# Grownetics_12_Channel_CT_Shield.net
KiCad netlist of a schematic drawn in EAGLE
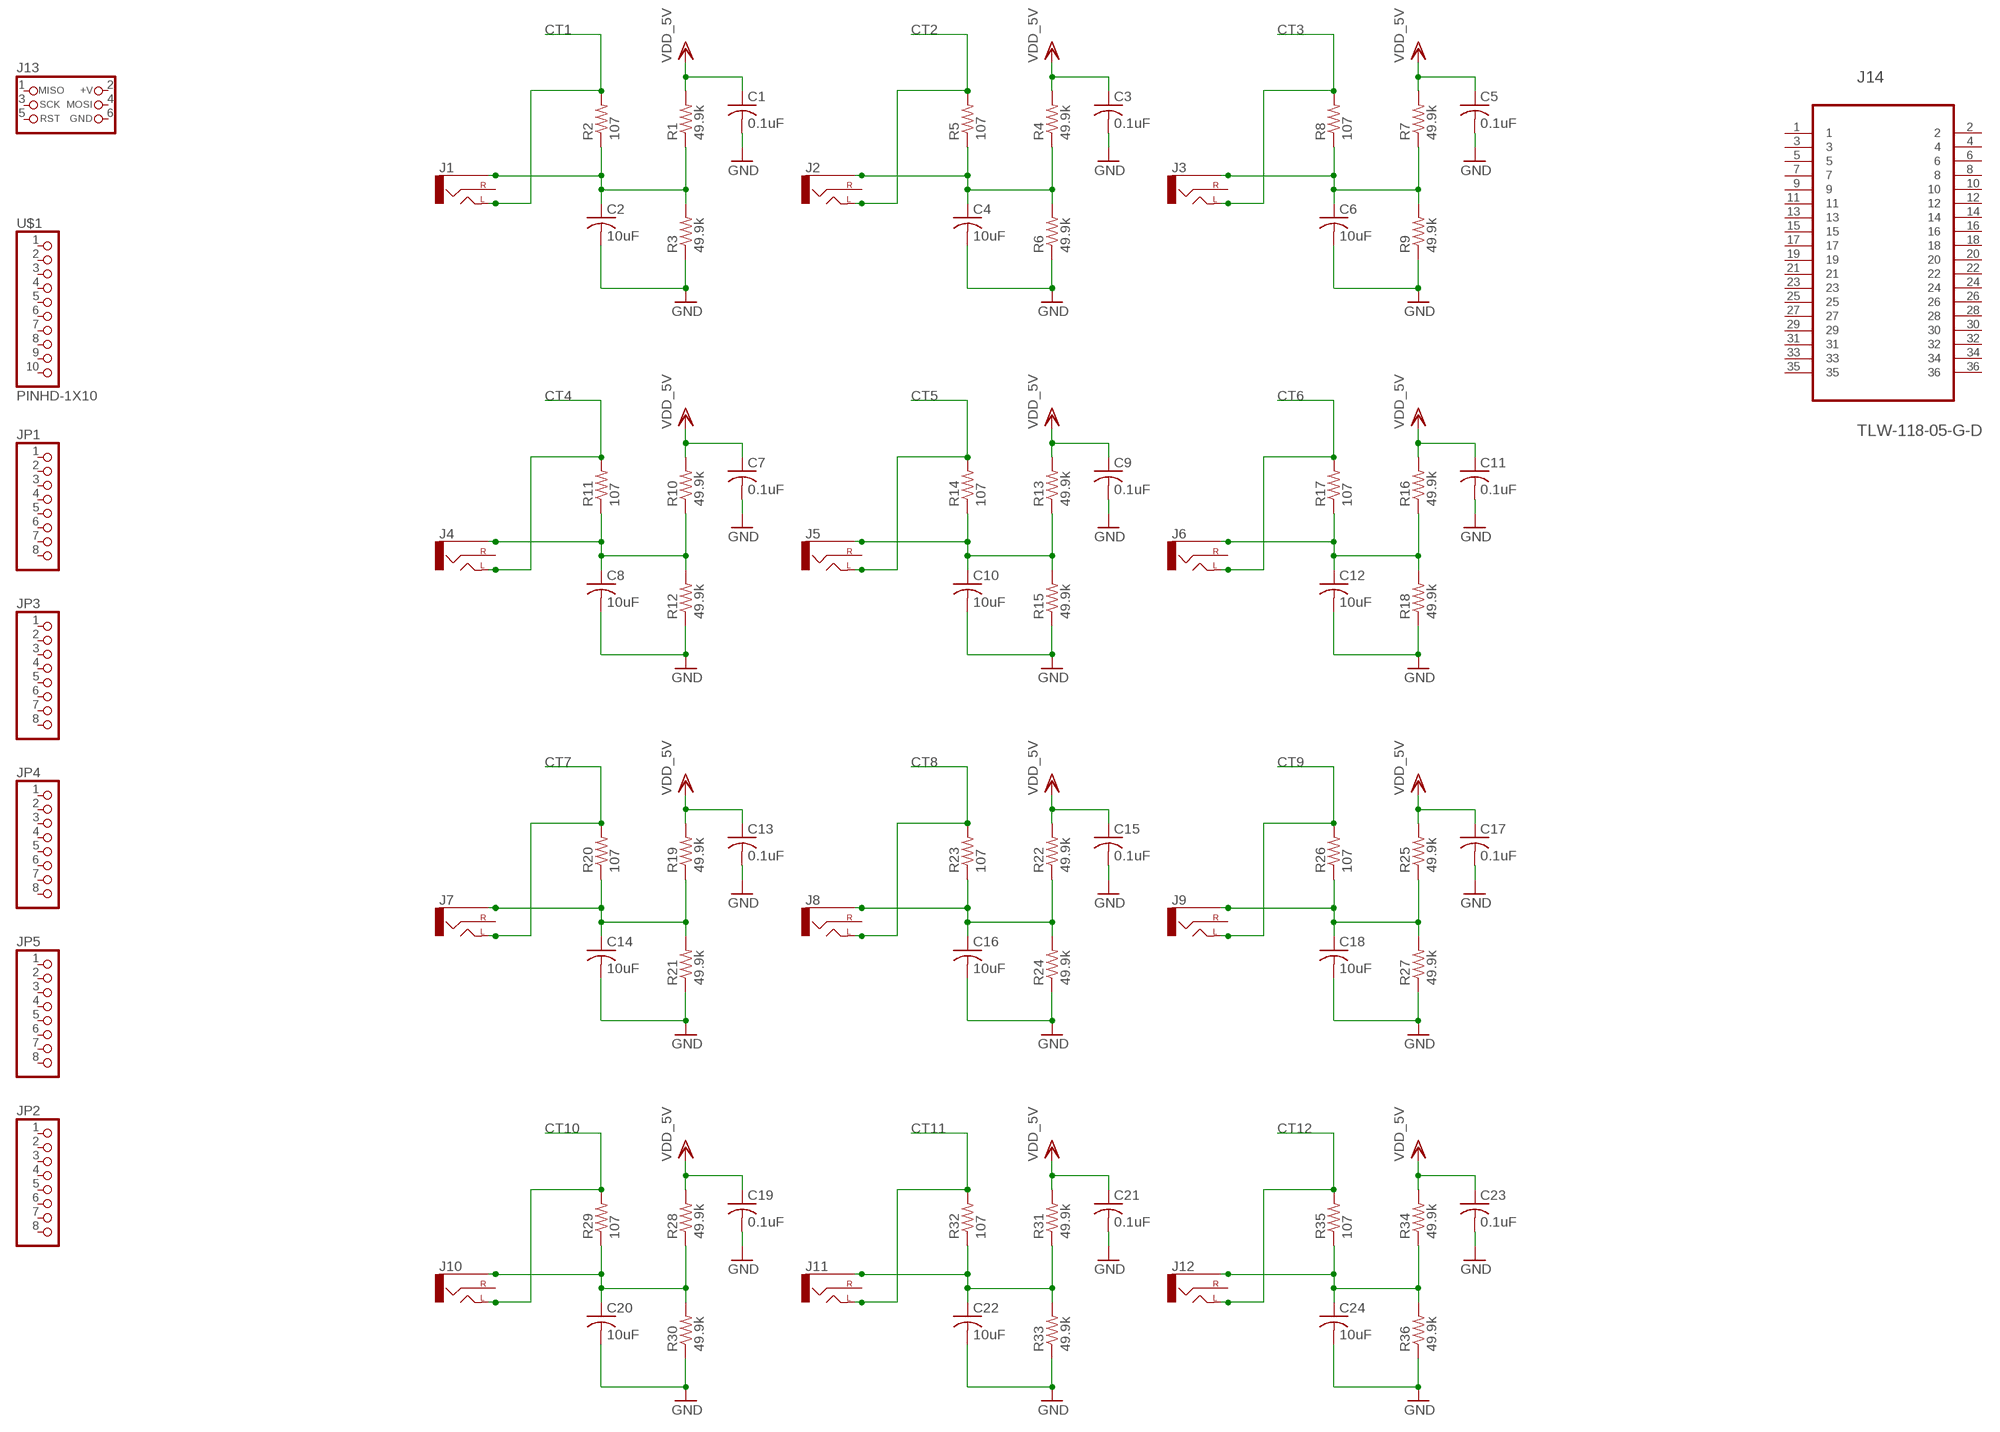
[diagram p0: schematic, sheet 1]

(export (version "E")
  (design (tool "Eeschema 10.0.6"))
  (components
    (comp (ref "C1")
      (value "0.1uF")
      (footprint "eagle-import:C0805")
      (libsource (lib "eagle-import") (part "C-USC0805"))
    )
    (comp (ref "C2")
      (value "10uF")
      (footprint "eagle-import:C0805")
      (libsource (lib "eagle-import") (part "C-USC0805"))
    )
    (comp (ref "C3")
      (value "0.1uF")
      (footprint "eagle-import:C0805")
      (libsource (lib "eagle-import") (part "C-USC0805"))
    )
    (comp (ref "C4")
      (value "10uF")
      (footprint "eagle-import:C0805")
      (libsource (lib "eagle-import") (part "C-USC0805"))
    )
    (comp (ref "C5")
      (value "0.1uF")
      (footprint "eagle-import:C0805")
      (libsource (lib "eagle-import") (part "C-USC0805"))
    )
    (comp (ref "C6")
      (value "10uF")
      (footprint "eagle-import:C0805")
      (libsource (lib "eagle-import") (part "C-USC0805"))
    )
    (comp (ref "C7")
      (value "0.1uF")
      (footprint "eagle-import:C0805")
      (libsource (lib "eagle-import") (part "C-USC0805"))
    )
    (comp (ref "C8")
      (value "10uF")
      (footprint "eagle-import:C0805")
      (libsource (lib "eagle-import") (part "C-USC0805"))
    )
    (comp (ref "C9")
      (value "0.1uF")
      (footprint "eagle-import:C0805")
      (libsource (lib "eagle-import") (part "C-USC0805"))
    )
    (comp (ref "C10")
      (value "10uF")
      (footprint "eagle-import:C0805")
      (libsource (lib "eagle-import") (part "C-USC0805"))
    )
    (comp (ref "C11")
      (value "0.1uF")
      (footprint "eagle-import:C0805")
      (libsource (lib "eagle-import") (part "C-USC0805"))
    )
    (comp (ref "C12")
      (value "10uF")
      (footprint "eagle-import:C0805")
      (libsource (lib "eagle-import") (part "C-USC0805"))
    )
    (comp (ref "C13")
      (value "0.1uF")
      (footprint "eagle-import:C0805")
      (libsource (lib "eagle-import") (part "C-USC0805"))
    )
    (comp (ref "C14")
      (value "10uF")
      (footprint "eagle-import:C0805")
      (libsource (lib "eagle-import") (part "C-USC0805"))
    )
    (comp (ref "C15")
      (value "0.1uF")
      (footprint "eagle-import:C0805")
      (libsource (lib "eagle-import") (part "C-USC0805"))
    )
    (comp (ref "C16")
      (value "10uF")
      (footprint "eagle-import:C0805")
      (libsource (lib "eagle-import") (part "C-USC0805"))
    )
    (comp (ref "C17")
      (value "0.1uF")
      (footprint "eagle-import:C0805")
      (libsource (lib "eagle-import") (part "C-USC0805"))
    )
    (comp (ref "C18")
      (value "10uF")
      (footprint "eagle-import:C0805")
      (libsource (lib "eagle-import") (part "C-USC0805"))
    )
    (comp (ref "C19")
      (value "0.1uF")
      (footprint "eagle-import:C0805")
      (libsource (lib "eagle-import") (part "C-USC0805"))
    )
    (comp (ref "C20")
      (value "10uF")
      (footprint "eagle-import:C0805")
      (libsource (lib "eagle-import") (part "C-USC0805"))
    )
    (comp (ref "C21")
      (value "0.1uF")
      (footprint "eagle-import:C0805")
      (libsource (lib "eagle-import") (part "C-USC0805"))
    )
    (comp (ref "C22")
      (value "10uF")
      (footprint "eagle-import:C0805")
      (libsource (lib "eagle-import") (part "C-USC0805"))
    )
    (comp (ref "C23")
      (value "0.1uF")
      (footprint "eagle-import:C0805")
      (libsource (lib "eagle-import") (part "C-USC0805"))
    )
    (comp (ref "C24")
      (value "10uF")
      (footprint "eagle-import:C0805")
      (libsource (lib "eagle-import") (part "C-USC0805"))
    )
    (comp (ref "J1")
      (value "AUDIO-JACKSMD2")
      (footprint "eagle-import:AUDIO-JACK-3.5MM-SMD")
      (libsource (lib "eagle-import") (part "AUDIO-JACKSMD2"))
    )
    (comp (ref "J2")
      (value "AUDIO-JACKSMD2")
      (footprint "eagle-import:AUDIO-JACK-3.5MM-SMD")
      (libsource (lib "eagle-import") (part "AUDIO-JACKSMD2"))
    )
    (comp (ref "J3")
      (value "AUDIO-JACKSMD2")
      (footprint "eagle-import:AUDIO-JACK-3.5MM-SMD")
      (libsource (lib "eagle-import") (part "AUDIO-JACKSMD2"))
    )
    (comp (ref "J4")
      (value "AUDIO-JACKSMD2")
      (footprint "eagle-import:AUDIO-JACK-3.5MM-SMD")
      (libsource (lib "eagle-import") (part "AUDIO-JACKSMD2"))
    )
    (comp (ref "J5")
      (value "AUDIO-JACKSMD2")
      (footprint "eagle-import:AUDIO-JACK-3.5MM-SMD")
      (libsource (lib "eagle-import") (part "AUDIO-JACKSMD2"))
    )
    (comp (ref "J6")
      (value "AUDIO-JACKSMD2")
      (footprint "eagle-import:AUDIO-JACK-3.5MM-SMD")
      (libsource (lib "eagle-import") (part "AUDIO-JACKSMD2"))
    )
    (comp (ref "J7")
      (value "AUDIO-JACKSMD2")
      (footprint "eagle-import:AUDIO-JACK-3.5MM-SMD")
      (libsource (lib "eagle-import") (part "AUDIO-JACKSMD2"))
    )
    (comp (ref "J8")
      (value "AUDIO-JACKSMD2")
      (footprint "eagle-import:AUDIO-JACK-3.5MM-SMD")
      (libsource (lib "eagle-import") (part "AUDIO-JACKSMD2"))
    )
    (comp (ref "J9")
      (value "AUDIO-JACKSMD2")
      (footprint "eagle-import:AUDIO-JACK-3.5MM-SMD")
      (libsource (lib "eagle-import") (part "AUDIO-JACKSMD2"))
    )
    (comp (ref "J10")
      (value "AUDIO-JACKSMD2")
      (footprint "eagle-import:AUDIO-JACK-3.5MM-SMD")
      (libsource (lib "eagle-import") (part "AUDIO-JACKSMD2"))
    )
    (comp (ref "J11")
      (value "AUDIO-JACKSMD2")
      (footprint "eagle-import:AUDIO-JACK-3.5MM-SMD")
      (libsource (lib "eagle-import") (part "AUDIO-JACKSMD2"))
    )
    (comp (ref "J12")
      (value "AUDIO-JACKSMD2")
      (footprint "eagle-import:AUDIO-JACK-3.5MM-SMD")
      (libsource (lib "eagle-import") (part "AUDIO-JACKSMD2"))
    )
    (comp (ref "J13")
      (value "CON_HEADER_PRG_AVR_ICSP-PTH")
      (footprint "eagle-import:HEADER_PRG_2X03")
      (libsource (lib "eagle-import") (part "CON_HEADER_PRG_AVR_ICSP-PTH"))
    )
    (comp (ref "J14")
      (value "TLW-118-05-G-D")
      (footprint "eagle-import:SAMTEC_TLW-118-05-G-D")
      (libsource (lib "eagle-import") (part "TLW-118-05-G-D"))
    )
    (comp (ref "JP1")
      (value "PINHD-1X8-3.5MM")
      (footprint "eagle-import:1X08-3.5MM")
      (libsource (lib "eagle-import") (part "PINHD-1X8-3.5MM"))
    )
    (comp (ref "JP2")
      (value "PINHD-1X8-3.5MM")
      (footprint "eagle-import:1X08-3.5MM")
      (libsource (lib "eagle-import") (part "PINHD-1X8-3.5MM"))
    )
    (comp (ref "JP3")
      (value "PINHD-1X8-3.5MM")
      (footprint "eagle-import:1X08-3.5MM")
      (libsource (lib "eagle-import") (part "PINHD-1X8-3.5MM"))
    )
    (comp (ref "JP4")
      (value "PINHD-1X8-3.5MM")
      (footprint "eagle-import:1X08-3.5MM")
      (libsource (lib "eagle-import") (part "PINHD-1X8-3.5MM"))
    )
    (comp (ref "JP5")
      (value "PINHD-1X8-3.5MM")
      (footprint "eagle-import:1X08-3.5MM")
      (libsource (lib "eagle-import") (part "PINHD-1X8-3.5MM"))
    )
    (comp (ref "R1")
      (value "49.9k")
      (footprint "eagle-import:M0805")
      (libsource (lib "eagle-import") (part "R-US_M0805"))
    )
    (comp (ref "R2")
      (value "107")
      (footprint "eagle-import:M0805")
      (libsource (lib "eagle-import") (part "R-US_M0805"))
    )
    (comp (ref "R3")
      (value "49.9k")
      (footprint "eagle-import:M0805")
      (libsource (lib "eagle-import") (part "R-US_M0805"))
    )
    (comp (ref "R4")
      (value "49.9k")
      (footprint "eagle-import:M0805")
      (libsource (lib "eagle-import") (part "R-US_M0805"))
    )
    (comp (ref "R5")
      (value "107")
      (footprint "eagle-import:M0805")
      (libsource (lib "eagle-import") (part "R-US_M0805"))
    )
    (comp (ref "R6")
      (value "49.9k")
      (footprint "eagle-import:M0805")
      (libsource (lib "eagle-import") (part "R-US_M0805"))
    )
    (comp (ref "R7")
      (value "49.9k")
      (footprint "eagle-import:M0805")
      (libsource (lib "eagle-import") (part "R-US_M0805"))
    )
    (comp (ref "R8")
      (value "107")
      (footprint "eagle-import:M0805")
      (libsource (lib "eagle-import") (part "R-US_M0805"))
    )
    (comp (ref "R9")
      (value "49.9k")
      (footprint "eagle-import:M0805")
      (libsource (lib "eagle-import") (part "R-US_M0805"))
    )
    (comp (ref "R10")
      (value "49.9k")
      (footprint "eagle-import:M0805")
      (libsource (lib "eagle-import") (part "R-US_M0805"))
    )
    (comp (ref "R11")
      (value "107")
      (footprint "eagle-import:M0805")
      (libsource (lib "eagle-import") (part "R-US_M0805"))
    )
    (comp (ref "R12")
      (value "49.9k")
      (footprint "eagle-import:M0805")
      (libsource (lib "eagle-import") (part "R-US_M0805"))
    )
    (comp (ref "R13")
      (value "49.9k")
      (footprint "eagle-import:M0805")
      (libsource (lib "eagle-import") (part "R-US_M0805"))
    )
    (comp (ref "R14")
      (value "107")
      (footprint "eagle-import:M0805")
      (libsource (lib "eagle-import") (part "R-US_M0805"))
    )
    (comp (ref "R15")
      (value "49.9k")
      (footprint "eagle-import:M0805")
      (libsource (lib "eagle-import") (part "R-US_M0805"))
    )
    (comp (ref "R16")
      (value "49.9k")
      (footprint "eagle-import:M0805")
      (libsource (lib "eagle-import") (part "R-US_M0805"))
    )
    (comp (ref "R17")
      (value "107")
      (footprint "eagle-import:M0805")
      (libsource (lib "eagle-import") (part "R-US_M0805"))
    )
    (comp (ref "R18")
      (value "49.9k")
      (footprint "eagle-import:M0805")
      (libsource (lib "eagle-import") (part "R-US_M0805"))
    )
    (comp (ref "R19")
      (value "49.9k")
      (footprint "eagle-import:M0805")
      (libsource (lib "eagle-import") (part "R-US_M0805"))
    )
    (comp (ref "R20")
      (value "107")
      (footprint "eagle-import:M0805")
      (libsource (lib "eagle-import") (part "R-US_M0805"))
    )
    (comp (ref "R21")
      (value "49.9k")
      (footprint "eagle-import:M0805")
      (libsource (lib "eagle-import") (part "R-US_M0805"))
    )
    (comp (ref "R22")
      (value "49.9k")
      (footprint "eagle-import:M0805")
      (libsource (lib "eagle-import") (part "R-US_M0805"))
    )
    (comp (ref "R23")
      (value "107")
      (footprint "eagle-import:M0805")
      (libsource (lib "eagle-import") (part "R-US_M0805"))
    )
    (comp (ref "R24")
      (value "49.9k")
      (footprint "eagle-import:M0805")
      (libsource (lib "eagle-import") (part "R-US_M0805"))
    )
    (comp (ref "R25")
      (value "49.9k")
      (footprint "eagle-import:M0805")
      (libsource (lib "eagle-import") (part "R-US_M0805"))
    )
    (comp (ref "R26")
      (value "107")
      (footprint "eagle-import:M0805")
      (libsource (lib "eagle-import") (part "R-US_M0805"))
    )
    (comp (ref "R27")
      (value "49.9k")
      (footprint "eagle-import:M0805")
      (libsource (lib "eagle-import") (part "R-US_M0805"))
    )
    (comp (ref "R28")
      (value "49.9k")
      (footprint "eagle-import:M0805")
      (libsource (lib "eagle-import") (part "R-US_M0805"))
    )
    (comp (ref "R29")
      (value "107")
      (footprint "eagle-import:M0805")
      (libsource (lib "eagle-import") (part "R-US_M0805"))
    )
    (comp (ref "R30")
      (value "49.9k")
      (footprint "eagle-import:M0805")
      (libsource (lib "eagle-import") (part "R-US_M0805"))
    )
    (comp (ref "R31")
      (value "49.9k")
      (footprint "eagle-import:M0805")
      (libsource (lib "eagle-import") (part "R-US_M0805"))
    )
    (comp (ref "R32")
      (value "107")
      (footprint "eagle-import:M0805")
      (libsource (lib "eagle-import") (part "R-US_M0805"))
    )
    (comp (ref "R33")
      (value "49.9k")
      (footprint "eagle-import:M0805")
      (libsource (lib "eagle-import") (part "R-US_M0805"))
    )
    (comp (ref "R34")
      (value "49.9k")
      (footprint "eagle-import:M0805")
      (libsource (lib "eagle-import") (part "R-US_M0805"))
    )
    (comp (ref "R35")
      (value "107")
      (footprint "eagle-import:M0805")
      (libsource (lib "eagle-import") (part "R-US_M0805"))
    )
    (comp (ref "R36")
      (value "49.9k")
      (footprint "eagle-import:M0805")
      (libsource (lib "eagle-import") (part "R-US_M0805"))
    )
    (comp (ref "U$1")
      (value "PINHD-1X10")
      (footprint "eagle-import:1X10-BIG")
      (libsource (lib "eagle-import") (part "PINHD-1X10"))
    )
  )
  (nets
    (net (code "1") (name "/CT1") (class "Default")
      (node (ref "J1") (pin "TIP") (pinfunction "LEFT_TIP") (pintype "bidirectional"))
      (node (ref "R2") (pin "2") (pinfunction "2_2") (pintype "passive"))
    )
    (net (code "2") (name "/CT2") (class "Default")
      (node (ref "J2") (pin "TIP") (pinfunction "LEFT_TIP") (pintype "bidirectional"))
      (node (ref "R5") (pin "2") (pinfunction "2_2") (pintype "passive"))
    )
    (net (code "3") (name "/CT3") (class "Default")
      (node (ref "J3") (pin "TIP") (pinfunction "LEFT_TIP") (pintype "bidirectional"))
      (node (ref "R8") (pin "2") (pinfunction "2_2") (pintype "passive"))
    )
    (net (code "4") (name "/CT4") (class "Default")
      (node (ref "J4") (pin "TIP") (pinfunction "LEFT_TIP") (pintype "bidirectional"))
      (node (ref "R11") (pin "2") (pinfunction "2_2") (pintype "passive"))
    )
    (net (code "5") (name "/CT5") (class "Default")
      (node (ref "J5") (pin "TIP") (pinfunction "LEFT_TIP") (pintype "bidirectional"))
      (node (ref "R14") (pin "2") (pinfunction "2_2") (pintype "passive"))
    )
    (net (code "6") (name "/CT6") (class "Default")
      (node (ref "J6") (pin "TIP") (pinfunction "LEFT_TIP") (pintype "bidirectional"))
      (node (ref "R17") (pin "2") (pinfunction "2_2") (pintype "passive"))
    )
    (net (code "7") (name "/CT7") (class "Default")
      (node (ref "J7") (pin "TIP") (pinfunction "LEFT_TIP") (pintype "bidirectional"))
      (node (ref "R20") (pin "2") (pinfunction "2_2") (pintype "passive"))
    )
    (net (code "8") (name "/CT8") (class "Default")
      (node (ref "J8") (pin "TIP") (pinfunction "LEFT_TIP") (pintype "bidirectional"))
      (node (ref "R23") (pin "2") (pinfunction "2_2") (pintype "passive"))
    )
    (net (code "9") (name "/CT9") (class "Default")
      (node (ref "J9") (pin "TIP") (pinfunction "LEFT_TIP") (pintype "bidirectional"))
      (node (ref "R26") (pin "2") (pinfunction "2_2") (pintype "passive"))
    )
    (net (code "10") (name "/CT10") (class "Default")
      (node (ref "J10") (pin "TIP") (pinfunction "LEFT_TIP") (pintype "bidirectional"))
      (node (ref "R29") (pin "2") (pinfunction "2_2") (pintype "passive"))
    )
    (net (code "11") (name "/CT11") (class "Default")
      (node (ref "J11") (pin "TIP") (pinfunction "LEFT_TIP") (pintype "bidirectional"))
      (node (ref "R32") (pin "2") (pinfunction "2_2") (pintype "passive"))
    )
    (net (code "12") (name "/CT12") (class "Default")
      (node (ref "J12") (pin "TIP") (pinfunction "LEFT_TIP") (pintype "bidirectional"))
      (node (ref "R35") (pin "2") (pinfunction "2_2") (pintype "passive"))
    )
    (net (code "13") (name "GND") (class "Default")
      (node (ref "C1") (pin "2") (pinfunction "2_2") (pintype "passive"))
      (node (ref "C10") (pin "2") (pinfunction "2_2") (pintype "passive"))
      (node (ref "C11") (pin "2") (pinfunction "2_2") (pintype "passive"))
      (node (ref "C12") (pin "2") (pinfunction "2_2") (pintype "passive"))
      (node (ref "C13") (pin "2") (pinfunction "2_2") (pintype "passive"))
      (node (ref "C14") (pin "2") (pinfunction "2_2") (pintype "passive"))
      (node (ref "C15") (pin "2") (pinfunction "2_2") (pintype "passive"))
      (node (ref "C16") (pin "2") (pinfunction "2_2") (pintype "passive"))
      (node (ref "C17") (pin "2") (pinfunction "2_2") (pintype "passive"))
      (node (ref "C18") (pin "2") (pinfunction "2_2") (pintype "passive"))
      (node (ref "C19") (pin "2") (pinfunction "2_2") (pintype "passive"))
      (node (ref "C2") (pin "2") (pinfunction "2_2") (pintype "passive"))
      (node (ref "C20") (pin "2") (pinfunction "2_2") (pintype "passive"))
      (node (ref "C21") (pin "2") (pinfunction "2_2") (pintype "passive"))
      (node (ref "C22") (pin "2") (pinfunction "2_2") (pintype "passive"))
      (node (ref "C23") (pin "2") (pinfunction "2_2") (pintype "passive"))
      (node (ref "C24") (pin "2") (pinfunction "2_2") (pintype "passive"))
      (node (ref "C3") (pin "2") (pinfunction "2_2") (pintype "passive"))
      (node (ref "C4") (pin "2") (pinfunction "2_2") (pintype "passive"))
      (node (ref "C5") (pin "2") (pinfunction "2_2") (pintype "passive"))
      (node (ref "C6") (pin "2") (pinfunction "2_2") (pintype "passive"))
      (node (ref "C7") (pin "2") (pinfunction "2_2") (pintype "passive"))
      (node (ref "C8") (pin "2") (pinfunction "2_2") (pintype "passive"))
      (node (ref "C9") (pin "2") (pinfunction "2_2") (pintype "passive"))
      (node (ref "R12") (pin "1") (pinfunction "1_1") (pintype "passive"))
      (node (ref "R15") (pin "1") (pinfunction "1_1") (pintype "passive"))
      (node (ref "R18") (pin "1") (pinfunction "1_1") (pintype "passive"))
      (node (ref "R21") (pin "1") (pinfunction "1_1") (pintype "passive"))
      (node (ref "R24") (pin "1") (pinfunction "1_1") (pintype "passive"))
      (node (ref "R27") (pin "1") (pinfunction "1_1") (pintype "passive"))
      (node (ref "R3") (pin "1") (pinfunction "1_1") (pintype "passive"))
      (node (ref "R30") (pin "1") (pinfunction "1_1") (pintype "passive"))
      (node (ref "R33") (pin "1") (pinfunction "1_1") (pintype "passive"))
      (node (ref "R36") (pin "1") (pinfunction "1_1") (pintype "passive"))
      (node (ref "R6") (pin "1") (pinfunction "1_1") (pintype "passive"))
      (node (ref "R9") (pin "1") (pinfunction "1_1") (pintype "passive"))
    )
    (net (code "14") (name "Net-(C2-Pad1)") (class "Default")
      (node (ref "C2") (pin "1") (pinfunction "1_1") (pintype "passive"))
      (node (ref "J1") (pin "SLEEVE") (pinfunction "SLEEVE_SLEEVE") (pintype "bidirectional"))
      (node (ref "R1") (pin "1") (pinfunction "1_1") (pintype "passive"))
      (node (ref "R2") (pin "1") (pinfunction "1_1") (pintype "passive"))
      (node (ref "R3") (pin "2") (pinfunction "2_2") (pintype "passive"))
    )
    (net (code "15") (name "Net-(C4-Pad1)") (class "Default")
      (node (ref "C4") (pin "1") (pinfunction "1_1") (pintype "passive"))
      (node (ref "J2") (pin "SLEEVE") (pinfunction "SLEEVE_SLEEVE") (pintype "bidirectional"))
      (node (ref "R4") (pin "1") (pinfunction "1_1") (pintype "passive"))
      (node (ref "R5") (pin "1") (pinfunction "1_1") (pintype "passive"))
      (node (ref "R6") (pin "2") (pinfunction "2_2") (pintype "passive"))
    )
    (net (code "16") (name "Net-(C6-Pad1)") (class "Default")
      (node (ref "C6") (pin "1") (pinfunction "1_1") (pintype "passive"))
      (node (ref "J3") (pin "SLEEVE") (pinfunction "SLEEVE_SLEEVE") (pintype "bidirectional"))
      (node (ref "R7") (pin "1") (pinfunction "1_1") (pintype "passive"))
      (node (ref "R8") (pin "1") (pinfunction "1_1") (pintype "passive"))
      (node (ref "R9") (pin "2") (pinfunction "2_2") (pintype "passive"))
    )
    (net (code "17") (name "Net-(C8-Pad1)") (class "Default")
      (node (ref "C8") (pin "1") (pinfunction "1_1") (pintype "passive"))
      (node (ref "J4") (pin "SLEEVE") (pinfunction "SLEEVE_SLEEVE") (pintype "bidirectional"))
      (node (ref "R10") (pin "1") (pinfunction "1_1") (pintype "passive"))
      (node (ref "R11") (pin "1") (pinfunction "1_1") (pintype "passive"))
      (node (ref "R12") (pin "2") (pinfunction "2_2") (pintype "passive"))
    )
    (net (code "18") (name "Net-(C10-Pad1)") (class "Default")
      (node (ref "C10") (pin "1") (pinfunction "1_1") (pintype "passive"))
      (node (ref "J5") (pin "SLEEVE") (pinfunction "SLEEVE_SLEEVE") (pintype "bidirectional"))
      (node (ref "R13") (pin "1") (pinfunction "1_1") (pintype "passive"))
      (node (ref "R14") (pin "1") (pinfunction "1_1") (pintype "passive"))
      (node (ref "R15") (pin "2") (pinfunction "2_2") (pintype "passive"))
    )
    (net (code "19") (name "Net-(C12-Pad1)") (class "Default")
      (node (ref "C12") (pin "1") (pinfunction "1_1") (pintype "passive"))
      (node (ref "J6") (pin "SLEEVE") (pinfunction "SLEEVE_SLEEVE") (pintype "bidirectional"))
      (node (ref "R16") (pin "1") (pinfunction "1_1") (pintype "passive"))
      (node (ref "R17") (pin "1") (pinfunction "1_1") (pintype "passive"))
      (node (ref "R18") (pin "2") (pinfunction "2_2") (pintype "passive"))
    )
    (net (code "20") (name "Net-(C14-Pad1)") (class "Default")
      (node (ref "C14") (pin "1") (pinfunction "1_1") (pintype "passive"))
      (node (ref "J7") (pin "SLEEVE") (pinfunction "SLEEVE_SLEEVE") (pintype "bidirectional"))
      (node (ref "R19") (pin "1") (pinfunction "1_1") (pintype "passive"))
      (node (ref "R20") (pin "1") (pinfunction "1_1") (pintype "passive"))
      (node (ref "R21") (pin "2") (pinfunction "2_2") (pintype "passive"))
    )
    (net (code "21") (name "Net-(C16-Pad1)") (class "Default")
      (node (ref "C16") (pin "1") (pinfunction "1_1") (pintype "passive"))
      (node (ref "J8") (pin "SLEEVE") (pinfunction "SLEEVE_SLEEVE") (pintype "bidirectional"))
      (node (ref "R22") (pin "1") (pinfunction "1_1") (pintype "passive"))
      (node (ref "R23") (pin "1") (pinfunction "1_1") (pintype "passive"))
      (node (ref "R24") (pin "2") (pinfunction "2_2") (pintype "passive"))
    )
    (net (code "22") (name "Net-(C18-Pad1)") (class "Default")
      (node (ref "C18") (pin "1") (pinfunction "1_1") (pintype "passive"))
      (node (ref "J9") (pin "SLEEVE") (pinfunction "SLEEVE_SLEEVE") (pintype "bidirectional"))
      (node (ref "R25") (pin "1") (pinfunction "1_1") (pintype "passive"))
      (node (ref "R26") (pin "1") (pinfunction "1_1") (pintype "passive"))
      (node (ref "R27") (pin "2") (pinfunction "2_2") (pintype "passive"))
    )
    (net (code "23") (name "Net-(C20-Pad1)") (class "Default")
      (node (ref "C20") (pin "1") (pinfunction "1_1") (pintype "passive"))
      (node (ref "J10") (pin "SLEEVE") (pinfunction "SLEEVE_SLEEVE") (pintype "bidirectional"))
      (node (ref "R28") (pin "1") (pinfunction "1_1") (pintype "passive"))
      (node (ref "R29") (pin "1") (pinfunction "1_1") (pintype "passive"))
      (node (ref "R30") (pin "2") (pinfunction "2_2") (pintype "passive"))
    )
    (net (code "24") (name "Net-(C22-Pad1)") (class "Default")
      (node (ref "C22") (pin "1") (pinfunction "1_1") (pintype "passive"))
      (node (ref "J11") (pin "SLEEVE") (pinfunction "SLEEVE_SLEEVE") (pintype "bidirectional"))
      (node (ref "R31") (pin "1") (pinfunction "1_1") (pintype "passive"))
      (node (ref "R32") (pin "1") (pinfunction "1_1") (pintype "passive"))
      (node (ref "R33") (pin "2") (pinfunction "2_2") (pintype "passive"))
    )
    (net (code "25") (name "Net-(C24-Pad1)") (class "Default")
      (node (ref "C24") (pin "1") (pinfunction "1_1") (pintype "passive"))
      (node (ref "J12") (pin "SLEEVE") (pinfunction "SLEEVE_SLEEVE") (pintype "bidirectional"))
      (node (ref "R34") (pin "1") (pinfunction "1_1") (pintype "passive"))
      (node (ref "R35") (pin "1") (pinfunction "1_1") (pintype "passive"))
      (node (ref "R36") (pin "2") (pinfunction "2_2") (pintype "passive"))
    )
    (net (code "26") (name "VDD_5V") (class "Default")
      (node (ref "C1") (pin "1") (pinfunction "1_1") (pintype "passive"))
      (node (ref "C11") (pin "1") (pinfunction "1_1") (pintype "passive"))
      (node (ref "C13") (pin "1") (pinfunction "1_1") (pintype "passive"))
      (node (ref "C15") (pin "1") (pinfunction "1_1") (pintype "passive"))
      (node (ref "C17") (pin "1") (pinfunction "1_1") (pintype "passive"))
      (node (ref "C19") (pin "1") (pinfunction "1_1") (pintype "passive"))
      (node (ref "C21") (pin "1") (pinfunction "1_1") (pintype "passive"))
      (node (ref "C23") (pin "1") (pinfunction "1_1") (pintype "passive"))
      (node (ref "C3") (pin "1") (pinfunction "1_1") (pintype "passive"))
      (node (ref "C5") (pin "1") (pinfunction "1_1") (pintype "passive"))
      (node (ref "C7") (pin "1") (pinfunction "1_1") (pintype "passive"))
      (node (ref "C9") (pin "1") (pinfunction "1_1") (pintype "passive"))
      (node (ref "R1") (pin "2") (pinfunction "2_2") (pintype "passive"))
      (node (ref "R10") (pin "2") (pinfunction "2_2") (pintype "passive"))
      (node (ref "R13") (pin "2") (pinfunction "2_2") (pintype "passive"))
      (node (ref "R16") (pin "2") (pinfunction "2_2") (pintype "passive"))
      (node (ref "R19") (pin "2") (pinfunction "2_2") (pintype "passive"))
      (node (ref "R22") (pin "2") (pinfunction "2_2") (pintype "passive"))
      (node (ref "R25") (pin "2") (pinfunction "2_2") (pintype "passive"))
      (node (ref "R28") (pin "2") (pinfunction "2_2") (pintype "passive"))
      (node (ref "R31") (pin "2") (pinfunction "2_2") (pintype "passive"))
      (node (ref "R34") (pin "2") (pinfunction "2_2") (pintype "passive"))
      (node (ref "R4") (pin "2") (pinfunction "2_2") (pintype "passive"))
      (node (ref "R7") (pin "2") (pinfunction "2_2") (pintype "passive"))
    )
    (net (code "27") (name "unconnected-(J1-RIGHT-PadRING)") (class "Default")
      (node (ref "J1") (pin "RING") (pinfunction "RIGHT_RING") (pintype "bidirectional"))
    )
    (net (code "28") (name "unconnected-(J2-RIGHT-PadRING)") (class "Default")
      (node (ref "J2") (pin "RING") (pinfunction "RIGHT_RING") (pintype "bidirectional"))
    )
    (net (code "29") (name "unconnected-(J3-RIGHT-PadRING)") (class "Default")
      (node (ref "J3") (pin "RING") (pinfunction "RIGHT_RING") (pintype "bidirectional"))
    )
    (net (code "30") (name "unconnected-(J4-RIGHT-PadRING)") (class "Default")
      (node (ref "J4") (pin "RING") (pinfunction "RIGHT_RING") (pintype "bidirectional"))
    )
    (net (code "31") (name "unconnected-(J5-RIGHT-PadRING)") (class "Default")
      (node (ref "J5") (pin "RING") (pinfunction "RIGHT_RING") (pintype "bidirectional"))
    )
    (net (code "32") (name "unconnected-(J6-RIGHT-PadRING)") (class "Default")
      (node (ref "J6") (pin "RING") (pinfunction "RIGHT_RING") (pintype "bidirectional"))
    )
    (net (code "33") (name "unconnected-(J7-RIGHT-PadRING)") (class "Default")
      (node (ref "J7") (pin "RING") (pinfunction "RIGHT_RING") (pintype "bidirectional"))
    )
    (net (code "34") (name "unconnected-(J8-RIGHT-PadRING)") (class "Default")
      (node (ref "J8") (pin "RING") (pinfunction "RIGHT_RING") (pintype "bidirectional"))
    )
    (net (code "35") (name "unconnected-(J9-RIGHT-PadRING)") (class "Default")
      (node (ref "J9") (pin "RING") (pinfunction "RIGHT_RING") (pintype "bidirectional"))
    )
    (net (code "36") (name "unconnected-(J10-RIGHT-PadRING)") (class "Default")
      (node (ref "J10") (pin "RING") (pinfunction "RIGHT_RING") (pintype "bidirectional"))
    )
    (net (code "37") (name "unconnected-(J11-RIGHT-PadRING)") (class "Default")
      (node (ref "J11") (pin "RING") (pinfunction "RIGHT_RING") (pintype "bidirectional"))
    )
    (net (code "38") (name "unconnected-(J12-RIGHT-PadRING)") (class "Default")
      (node (ref "J12") (pin "RING") (pinfunction "RIGHT_RING") (pintype "bidirectional"))
    )
    (net (code "39") (name "unconnected-(J13-+V-Pad2)") (class "Default")
      (node (ref "J13") (pin "2") (pinfunction "+V_2") (pintype "passive"))
    )
    (net (code "40") (name "unconnected-(J13-GND-Pad6)") (class "Default")
      (node (ref "J13") (pin "6") (pinfunction "GND_6") (pintype "passive"))
    )
    (net (code "41") (name "unconnected-(J13-MISO-Pad1)") (class "Default")
      (node (ref "J13") (pin "1") (pinfunction "MISO_1") (pintype "passive"))
    )
    (net (code "42") (name "unconnected-(J13-MOSI-Pad4)") (class "Default")
      (node (ref "J13") (pin "4") (pinfunction "MOSI_4") (pintype "passive"))
    )
    (net (code "43") (name "unconnected-(J13-RST-Pad5)") (class "Default")
      (node (ref "J13") (pin "5") (pinfunction "RST_5") (pintype "passive"))
    )
    (net (code "44") (name "unconnected-(J13-SCK-Pad3)") (class "Default")
      (node (ref "J13") (pin "3") (pinfunction "SCK_3") (pintype "passive"))
    )
    (net (code "45") (name "unconnected-(J14-Pad1)") (class "Default")
      (node (ref "J14") (pin "1") (pinfunction "1_1") (pintype "passive"))
    )
    (net (code "46") (name "unconnected-(J14-Pad2)") (class "Default")
      (node (ref "J14") (pin "2") (pinfunction "2_2") (pintype "passive"))
    )
    (net (code "47") (name "unconnected-(J14-Pad3)") (class "Default")
      (node (ref "J14") (pin "3") (pinfunction "3_3") (pintype "passive"))
    )
    (net (code "48") (name "unconnected-(J14-Pad4)") (class "Default")
      (node (ref "J14") (pin "4") (pinfunction "4_4") (pintype "passive"))
    )
    (net (code "49") (name "unconnected-(J14-Pad5)") (class "Default")
      (node (ref "J14") (pin "5") (pinfunction "5_5") (pintype "passive"))
    )
    (net (code "50") (name "unconnected-(J14-Pad6)") (class "Default")
      (node (ref "J14") (pin "6") (pinfunction "6_6") (pintype "passive"))
    )
    (net (code "51") (name "unconnected-(J14-Pad7)") (class "Default")
      (node (ref "J14") (pin "7") (pinfunction "7_7") (pintype "passive"))
    )
    (net (code "52") (name "unconnected-(J14-Pad8)") (class "Default")
      (node (ref "J14") (pin "8") (pinfunction "8_8") (pintype "passive"))
    )
    (net (code "53") (name "unconnected-(J14-Pad9)") (class "Default")
      (node (ref "J14") (pin "9") (pinfunction "9_9") (pintype "passive"))
    )
    (net (code "54") (name "unconnected-(J14-Pad10)") (class "Default")
      (node (ref "J14") (pin "10") (pinfunction "10_10") (pintype "passive"))
    )
    (net (code "55") (name "unconnected-(J14-Pad11)") (class "Default")
      (node (ref "J14") (pin "11") (pinfunction "11_11") (pintype "passive"))
    )
    (net (code "56") (name "unconnected-(J14-Pad12)") (class "Default")
      (node (ref "J14") (pin "12") (pinfunction "12_12") (pintype "passive"))
    )
    (net (code "57") (name "unconnected-(J14-Pad13)") (class "Default")
      (node (ref "J14") (pin "13") (pinfunction "13_13") (pintype "passive"))
    )
    (net (code "58") (name "unconnected-(J14-Pad14)") (class "Default")
      (node (ref "J14") (pin "14") (pinfunction "14_14") (pintype "passive"))
    )
    (net (code "59") (name "unconnected-(J14-Pad15)") (class "Default")
      (node (ref "J14") (pin "15") (pinfunction "15_15") (pintype "passive"))
    )
    (net (code "60") (name "unconnected-(J14-Pad16)") (class "Default")
      (node (ref "J14") (pin "16") (pinfunction "16_16") (pintype "passive"))
    )
    (net (code "61") (name "unconnected-(J14-Pad17)") (class "Default")
      (node (ref "J14") (pin "17") (pinfunction "17_17") (pintype "passive"))
    )
    (net (code "62") (name "unconnected-(J14-Pad18)") (class "Default")
      (node (ref "J14") (pin "18") (pinfunction "18_18") (pintype "passive"))
    )
    (net (code "63") (name "unconnected-(J14-Pad19)") (class "Default")
      (node (ref "J14") (pin "19") (pinfunction "19_19") (pintype "passive"))
    )
    (net (code "64") (name "unconnected-(J14-Pad20)") (class "Default")
      (node (ref "J14") (pin "20") (pinfunction "20_20") (pintype "passive"))
    )
    (net (code "65") (name "unconnected-(J14-Pad21)") (class "Default")
      (node (ref "J14") (pin "21") (pinfunction "21_21") (pintype "passive"))
    )
    (net (code "66") (name "unconnected-(J14-Pad22)") (class "Default")
      (node (ref "J14") (pin "22") (pinfunction "22_22") (pintype "passive"))
    )
    (net (code "67") (name "unconnected-(J14-Pad23)") (class "Default")
      (node (ref "J14") (pin "23") (pinfunction "23_23") (pintype "passive"))
    )
    (net (code "68") (name "unconnected-(J14-Pad24)") (class "Default")
      (node (ref "J14") (pin "24") (pinfunction "24_24") (pintype "passive"))
    )
    (net (code "69") (name "unconnected-(J14-Pad25)") (class "Default")
      (node (ref "J14") (pin "25") (pinfunction "25_25") (pintype "passive"))
    )
    (net (code "70") (name "unconnected-(J14-Pad26)") (class "Default")
      (node (ref "J14") (pin "26") (pinfunction "26_26") (pintype "passive"))
    )
    (net (code "71") (name "unconnected-(J14-Pad27)") (class "Default")
      (node (ref "J14") (pin "27") (pinfunction "27_27") (pintype "passive"))
    )
    (net (code "72") (name "unconnected-(J14-Pad28)") (class "Default")
      (node (ref "J14") (pin "28") (pinfunction "28_28") (pintype "passive"))
    )
    (net (code "73") (name "unconnected-(J14-Pad29)") (class "Default")
      (node (ref "J14") (pin "29") (pinfunction "29_29") (pintype "passive"))
    )
    (net (code "74") (name "unconnected-(J14-Pad30)") (class "Default")
      (node (ref "J14") (pin "30") (pinfunction "30_30") (pintype "passive"))
    )
    (net (code "75") (name "unconnected-(J14-Pad31)") (class "Default")
      (node (ref "J14") (pin "31") (pinfunction "31_31") (pintype "passive"))
    )
    (net (code "76") (name "unconnected-(J14-Pad32)") (class "Default")
      (node (ref "J14") (pin "32") (pinfunction "32_32") (pintype "passive"))
    )
    (net (code "77") (name "unconnected-(J14-Pad33)") (class "Default")
      (node (ref "J14") (pin "33") (pinfunction "33_33") (pintype "passive"))
    )
    (net (code "78") (name "unconnected-(J14-Pad34)") (class "Default")
      (node (ref "J14") (pin "34") (pinfunction "34_34") (pintype "passive"))
    )
    (net (code "79") (name "unconnected-(J14-Pad35)") (class "Default")
      (node (ref "J14") (pin "35") (pinfunction "35_35") (pintype "passive"))
    )
    (net (code "80") (name "unconnected-(J14-Pad36)") (class "Default")
      (node (ref "J14") (pin "36") (pinfunction "36_36") (pintype "passive"))
    )
    (net (code "81") (name "unconnected-(JP1-Pad1)") (class "Default")
      (node (ref "JP1") (pin "1") (pinfunction "1_1") (pintype "passive"))
    )
    (net (code "82") (name "unconnected-(JP1-Pad2)") (class "Default")
      (node (ref "JP1") (pin "2") (pinfunction "2_2") (pintype "passive"))
    )
    (net (code "83") (name "unconnected-(JP1-Pad3)") (class "Default")
      (node (ref "JP1") (pin "3") (pinfunction "3_3") (pintype "passive"))
    )
    (net (code "84") (name "unconnected-(JP1-Pad4)") (class "Default")
      (node (ref "JP1") (pin "4") (pinfunction "4_4") (pintype "passive"))
    )
    (net (code "85") (name "unconnected-(JP1-Pad5)") (class "Default")
      (node (ref "JP1") (pin "5") (pinfunction "5_5") (pintype "passive"))
    )
    (net (code "86") (name "unconnected-(JP1-Pad6)") (class "Default")
      (node (ref "JP1") (pin "6") (pinfunction "6_6") (pintype "passive"))
    )
    (net (code "87") (name "unconnected-(JP1-Pad7)") (class "Default")
      (node (ref "JP1") (pin "7") (pinfunction "7_7") (pintype "passive"))
    )
    (net (code "88") (name "unconnected-(JP1-Pad8)") (class "Default")
      (node (ref "JP1") (pin "8") (pinfunction "8_8") (pintype "passive"))
    )
    (net (code "89") (name "unconnected-(JP2-Pad1)") (class "Default")
      (node (ref "JP2") (pin "1") (pinfunction "1_1") (pintype "passive"))
    )
    (net (code "90") (name "unconnected-(JP2-Pad2)") (class "Default")
      (node (ref "JP2") (pin "2") (pinfunction "2_2") (pintype "passive"))
    )
    (net (code "91") (name "unconnected-(JP2-Pad3)") (class "Default")
      (node (ref "JP2") (pin "3") (pinfunction "3_3") (pintype "passive"))
    )
    (net (code "92") (name "unconnected-(JP2-Pad4)") (class "Default")
      (node (ref "JP2") (pin "4") (pinfunction "4_4") (pintype "passive"))
    )
    (net (code "93") (name "unconnected-(JP2-Pad5)") (class "Default")
      (node (ref "JP2") (pin "5") (pinfunction "5_5") (pintype "passive"))
    )
    (net (code "94") (name "unconnected-(JP2-Pad6)") (class "Default")
      (node (ref "JP2") (pin "6") (pinfunction "6_6") (pintype "passive"))
    )
    (net (code "95") (name "unconnected-(JP2-Pad7)") (class "Default")
      (node (ref "JP2") (pin "7") (pinfunction "7_7") (pintype "passive"))
    )
    (net (code "96") (name "unconnected-(JP2-Pad8)") (class "Default")
      (node (ref "JP2") (pin "8") (pinfunction "8_8") (pintype "passive"))
    )
    (net (code "97") (name "unconnected-(JP3-Pad1)") (class "Default")
      (node (ref "JP3") (pin "1") (pinfunction "1_1") (pintype "passive"))
    )
    (net (code "98") (name "unconnected-(JP3-Pad2)") (class "Default")
      (node (ref "JP3") (pin "2") (pinfunction "2_2") (pintype "passive"))
    )
    (net (code "99") (name "unconnected-(JP3-Pad3)") (class "Default")
      (node (ref "JP3") (pin "3") (pinfunction "3_3") (pintype "passive"))
    )
    (net (code "100") (name "unconnected-(JP3-Pad4)") (class "Default")
      (node (ref "JP3") (pin "4") (pinfunction "4_4") (pintype "passive"))
    )
    (net (code "101") (name "unconnected-(JP3-Pad5)") (class "Default")
      (node (ref "JP3") (pin "5") (pinfunction "5_5") (pintype "passive"))
    )
    (net (code "102") (name "unconnected-(JP3-Pad6)") (class "Default")
      (node (ref "JP3") (pin "6") (pinfunction "6_6") (pintype "passive"))
    )
    (net (code "103") (name "unconnected-(JP3-Pad7)") (class "Default")
      (node (ref "JP3") (pin "7") (pinfunction "7_7") (pintype "passive"))
    )
    (net (code "104") (name "unconnected-(JP3-Pad8)") (class "Default")
      (node (ref "JP3") (pin "8") (pinfunction "8_8") (pintype "passive"))
    )
    (net (code "105") (name "unconnected-(JP4-Pad1)") (class "Default")
      (node (ref "JP4") (pin "1") (pinfunction "1_1") (pintype "passive"))
    )
    (net (code "106") (name "unconnected-(JP4-Pad2)") (class "Default")
      (node (ref "JP4") (pin "2") (pinfunction "2_2") (pintype "passive"))
    )
    (net (code "107") (name "unconnected-(JP4-Pad3)") (class "Default")
      (node (ref "JP4") (pin "3") (pinfunction "3_3") (pintype "passive"))
    )
    (net (code "108") (name "unconnected-(JP4-Pad4)") (class "Default")
      (node (ref "JP4") (pin "4") (pinfunction "4_4") (pintype "passive"))
    )
    (net (code "109") (name "unconnected-(JP4-Pad5)") (class "Default")
      (node (ref "JP4") (pin "5") (pinfunction "5_5") (pintype "passive"))
    )
    (net (code "110") (name "unconnected-(JP4-Pad6)") (class "Default")
      (node (ref "JP4") (pin "6") (pinfunction "6_6") (pintype "passive"))
    )
    (net (code "111") (name "unconnected-(JP4-Pad7)") (class "Default")
      (node (ref "JP4") (pin "7") (pinfunction "7_7") (pintype "passive"))
    )
    (net (code "112") (name "unconnected-(JP4-Pad8)") (class "Default")
      (node (ref "JP4") (pin "8") (pinfunction "8_8") (pintype "passive"))
    )
    (net (code "113") (name "unconnected-(JP5-Pad1)") (class "Default")
      (node (ref "JP5") (pin "1") (pinfunction "1_1") (pintype "passive"))
    )
    (net (code "114") (name "unconnected-(JP5-Pad2)") (class "Default")
      (node (ref "JP5") (pin "2") (pinfunction "2_2") (pintype "passive"))
    )
    (net (code "115") (name "unconnected-(JP5-Pad3)") (class "Default")
      (node (ref "JP5") (pin "3") (pinfunction "3_3") (pintype "passive"))
    )
    (net (code "116") (name "unconnected-(JP5-Pad4)") (class "Default")
      (node (ref "JP5") (pin "4") (pinfunction "4_4") (pintype "passive"))
    )
    (net (code "117") (name "unconnected-(JP5-Pad5)") (class "Default")
      (node (ref "JP5") (pin "5") (pinfunction "5_5") (pintype "passive"))
    )
    (net (code "118") (name "unconnected-(JP5-Pad6)") (class "Default")
      (node (ref "JP5") (pin "6") (pinfunction "6_6") (pintype "passive"))
    )
    (net (code "119") (name "unconnected-(JP5-Pad7)") (class "Default")
      (node (ref "JP5") (pin "7") (pinfunction "7_7") (pintype "passive"))
    )
    (net (code "120") (name "unconnected-(JP5-Pad8)") (class "Default")
      (node (ref "JP5") (pin "8") (pinfunction "8_8") (pintype "passive"))
    )
    (net (code "121") (name "unconnected-(U$1-Pad1)") (class "Default")
      (node (ref "U$1") (pin "1") (pinfunction "1_1") (pintype "passive"))
    )
    (net (code "122") (name "unconnected-(U$1-Pad2)") (class "Default")
      (node (ref "U$1") (pin "2") (pinfunction "2_2") (pintype "passive"))
    )
    (net (code "123") (name "unconnected-(U$1-Pad3)") (class "Default")
      (node (ref "U$1") (pin "3") (pinfunction "3_3") (pintype "passive"))
    )
    (net (code "124") (name "unconnected-(U$1-Pad4)") (class "Default")
      (node (ref "U$1") (pin "4") (pinfunction "4_4") (pintype "passive"))
    )
    (net (code "125") (name "unconnected-(U$1-Pad5)") (class "Default")
      (node (ref "U$1") (pin "5") (pinfunction "5_5") (pintype "passive"))
    )
    (net (code "126") (name "unconnected-(U$1-Pad6)") (class "Default")
      (node (ref "U$1") (pin "6") (pinfunction "6_6") (pintype "passive"))
    )
    (net (code "127") (name "unconnected-(U$1-Pad7)") (class "Default")
      (node (ref "U$1") (pin "7") (pinfunction "7_7") (pintype "passive"))
    )
    (net (code "128") (name "unconnected-(U$1-Pad8)") (class "Default")
      (node (ref "U$1") (pin "8") (pinfunction "8_8") (pintype "passive"))
    )
    (net (code "129") (name "unconnected-(U$1-Pad9)") (class "Default")
      (node (ref "U$1") (pin "9") (pinfunction "9_9") (pintype "passive"))
    )
    (net (code "130") (name "unconnected-(U$1-Pad10)") (class "Default")
      (node (ref "U$1") (pin "10") (pinfunction "10_10") (pintype "passive"))
    )
  )
)
